# GBASP_USB-C.net
KiCad netlist of a schematic drawn in EAGLE
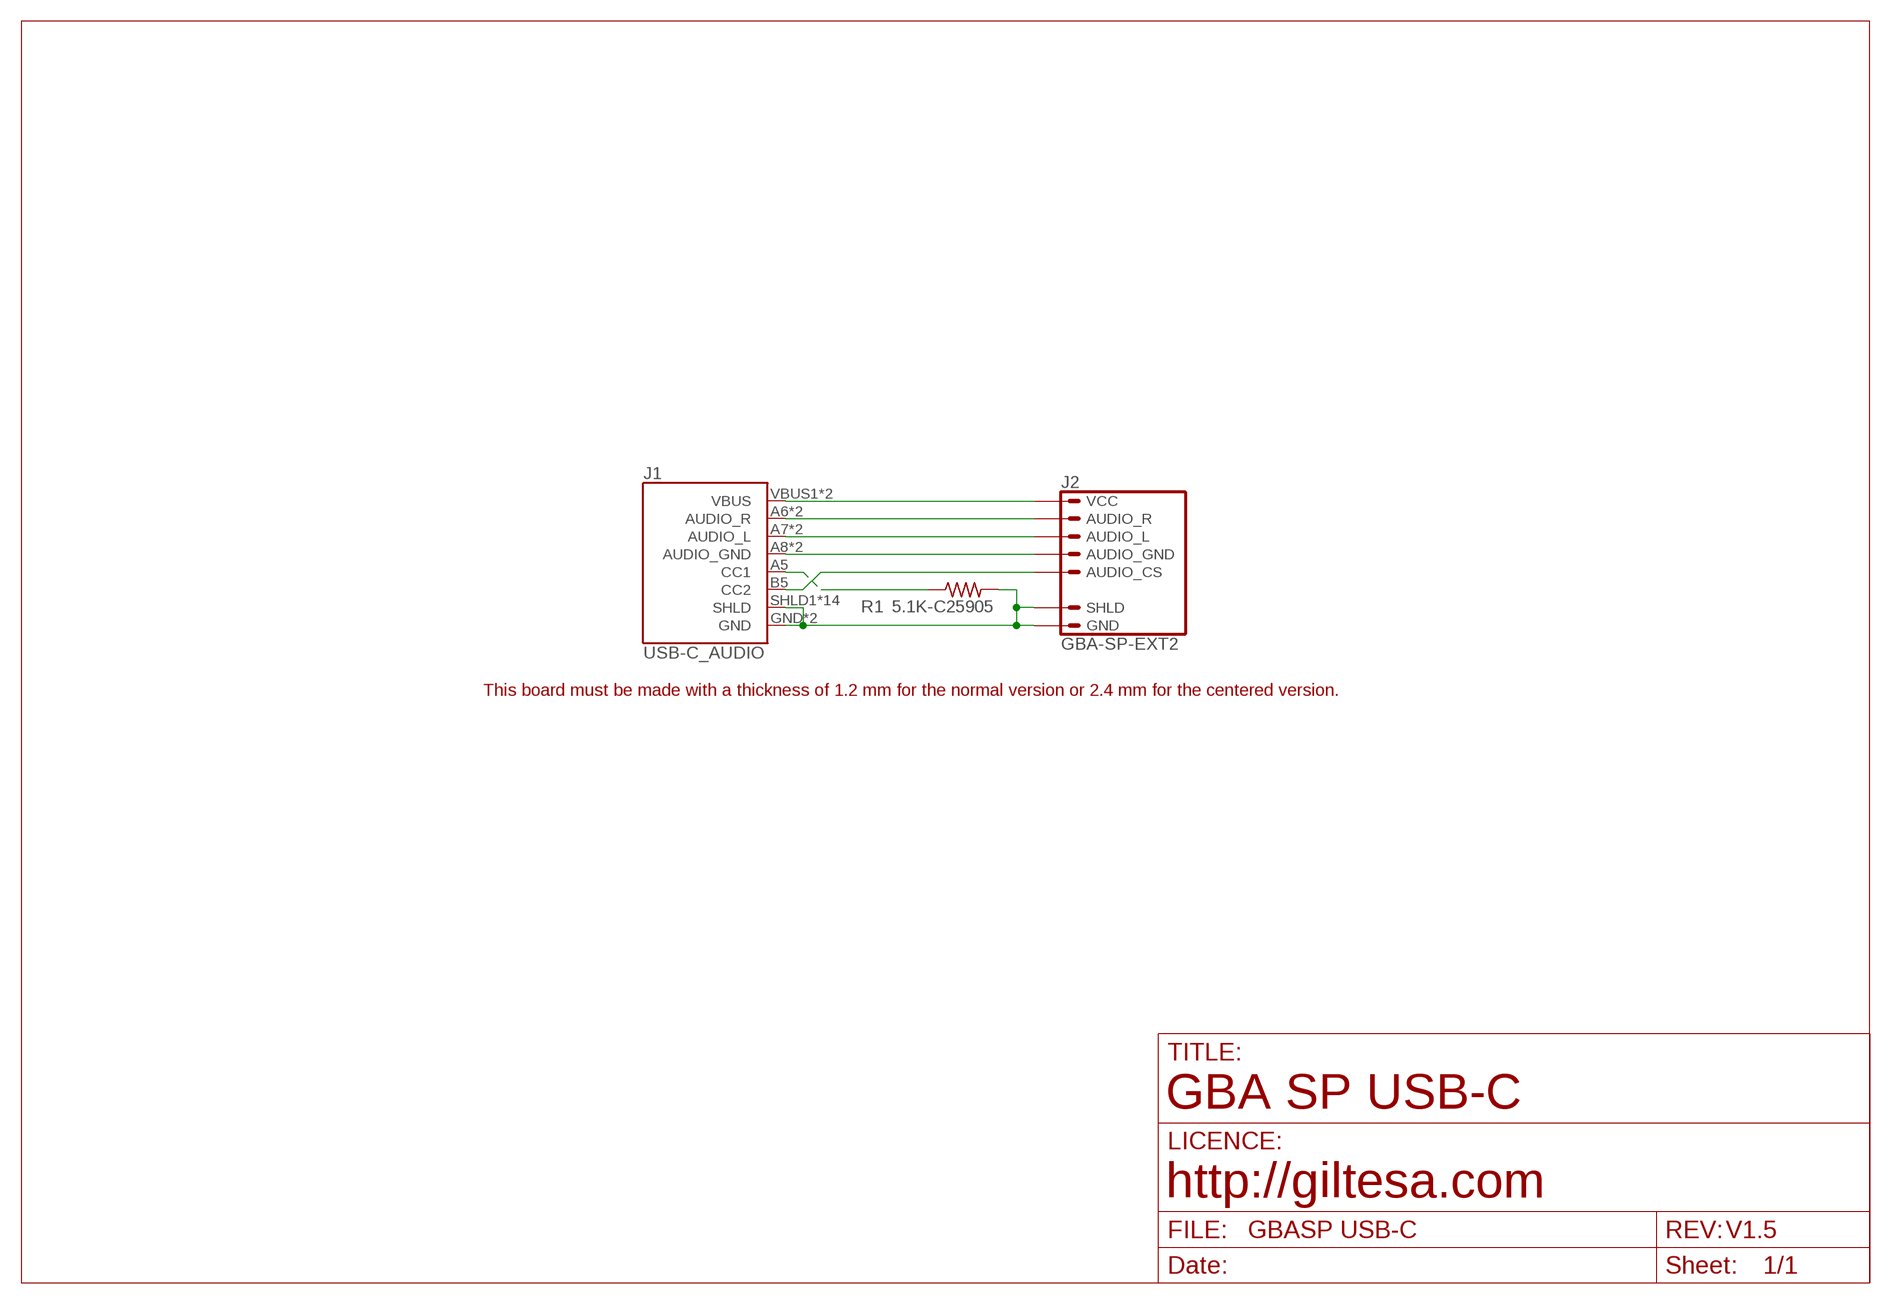
[diagram p0: schematic, sheet 1]

(export (version "E")
  (design (tool "Eeschema 10.0.6"))
  (components
    (comp (ref "J1")
      (value "USB-C_AUDIO")
      (footprint "eagle-import:USB-C_16P_3SHLD_DRILL")
      (libsource (lib "eagle-import") (part "USB-C_POWER_AUDIOGBASP_DRILL"))
    )
    (comp (ref "J2")
      (value "GBA-SP-EXT2")
      (footprint "eagle-import:GBA-SP-EXT2_1")
      (libsource (lib "eagle-import") (part "GBA-SP-EXT2_1"))
    )
    (comp (ref "R1")
      (value "5.1K-C25905")
      (footprint "eagle-import:R0402")
      (libsource (lib "eagle-import") (part "R0402"))
    )
  )
  (nets
    (net (code "1") (name "Net-(J1-AUDIO_GND-PadA8)") (class "Default")
      (node (ref "J1") (pin "A8") (pinfunction "AUDIO_GND_A8") (pintype "bidirectional"))
      (node (ref "J1") (pin "B8") (pinfunction "AUDIO_GND_B8") (pintype "bidirectional"))
      (node (ref "J2") (pin "AUDIO_GND") (pinfunction "AUDIO_GND_AUDIO_GND") (pintype "passive"))
    )
    (net (code "2") (name "Net-(J1-AUDIO_L-PadA7)") (class "Default")
      (node (ref "J1") (pin "A7") (pinfunction "AUDIO_L_A7") (pintype "bidirectional"))
      (node (ref "J1") (pin "B7") (pinfunction "AUDIO_L_B7") (pintype "bidirectional"))
      (node (ref "J2") (pin "AUDIO_L") (pinfunction "AUDIO_L_AUDIO_L") (pintype "passive"))
    )
    (net (code "3") (name "Net-(J1-AUDIO_R-PadA6)") (class "Default")
      (node (ref "J1") (pin "A6") (pinfunction "AUDIO_R_A6") (pintype "bidirectional"))
      (node (ref "J1") (pin "B6") (pinfunction "AUDIO_R_B6") (pintype "bidirectional"))
      (node (ref "J2") (pin "AUDIO_R") (pinfunction "AUDIO_R_AUDIO_R") (pintype "passive"))
    )
    (net (code "4") (name "Net-(J1-CC1)") (class "Default")
      (node (ref "J1") (pin "A5") (pinfunction "CC1_A5") (pintype "bidirectional"))
      (node (ref "R1") (pin "1") (pinfunction "1_1") (pintype "passive"))
    )
    (net (code "5") (name "Net-(J1-CC2)") (class "Default")
      (node (ref "J1") (pin "B5") (pinfunction "CC2_B5") (pintype "bidirectional"))
      (node (ref "J2") (pin "AUDIO_CS") (pinfunction "AUDIO_CS_AUDIO_CS") (pintype "passive"))
    )
    (net (code "6") (name "Net-(J1-GND-PadGND2)") (class "Default")
      (node (ref "J1") (pin "GND") (pinfunction "GND_GND") (pintype "bidirectional"))
      (node (ref "J1") (pin "GND2") (pinfunction "GND_GND2") (pintype "bidirectional"))
      (node (ref "J1") (pin "SHLD1") (pinfunction "SHLD_SHLD1") (pintype "bidirectional"))
      (node (ref "J1") (pin "SHLD1_2") (pinfunction "SHLD_SHLD1_2") (pintype "bidirectional"))
      (node (ref "J1") (pin "SHLD3") (pinfunction "SHLD_SHLD3") (pintype "bidirectional"))
      (node (ref "J1") (pin "SHLD3_2") (pinfunction "SHLD_SHLD3_2") (pintype "bidirectional"))
      (node (ref "J1") (pin "SHLD4") (pinfunction "SHLD_SHLD4") (pintype "bidirectional"))
      (node (ref "J1") (pin "SHLD4_2") (pinfunction "SHLD_SHLD4_2") (pintype "bidirectional"))
      (node (ref "J1") (pin "SHLD5") (pinfunction "SHLD_SHLD5") (pintype "bidirectional"))
      (node (ref "J1") (pin "SHLD5_2") (pinfunction "SHLD_SHLD5_2") (pintype "bidirectional"))
      (node (ref "J1") (pin "SHLD6") (pinfunction "SHLD_SHLD6") (pintype "bidirectional"))
      (node (ref "J1") (pin "SHLD6_2") (pinfunction "SHLD_SHLD6_2") (pintype "bidirectional"))
      (node (ref "J1") (pin "SHLD7") (pinfunction "SHLD_SHLD7") (pintype "bidirectional"))
      (node (ref "J1") (pin "SHLD7_2") (pinfunction "SHLD_SHLD7_2") (pintype "bidirectional"))
      (node (ref "J1") (pin "SHLD8") (pinfunction "SHLD_SHLD8") (pintype "bidirectional"))
      (node (ref "J1") (pin "SHLD8_2") (pinfunction "SHLD_SHLD8_2") (pintype "bidirectional"))
      (node (ref "J2") (pin "GND") (pinfunction "GND_GND") (pintype "passive"))
      (node (ref "J2") (pin "SHLD1") (pinfunction "SHLD_SHLD1") (pintype "passive"))
      (node (ref "J2") (pin "SHLD2") (pinfunction "SHLD_SHLD2") (pintype "passive"))
      (node (ref "J2") (pin "SHLD3") (pinfunction "SHLD_SHLD3") (pintype "passive"))
      (node (ref "J2") (pin "SHLD4") (pinfunction "SHLD_SHLD4") (pintype "passive"))
      (node (ref "R1") (pin "2") (pinfunction "2_2") (pintype "passive"))
    )
    (net (code "7") (name "Net-(J1-VBUS-PadVBUS1)") (class "Default")
      (node (ref "J1") (pin "VBUS1") (pinfunction "VBUS_VBUS1") (pintype "bidirectional"))
      (node (ref "J1") (pin "VBUS2") (pinfunction "VBUS_VBUS2") (pintype "bidirectional"))
      (node (ref "J2") (pin "VCC") (pinfunction "VCC_VCC") (pintype "passive"))
    )
  )
)
